# RelayBoard-Large-v11.net
KiCad netlist of a schematic drawn in EAGLE
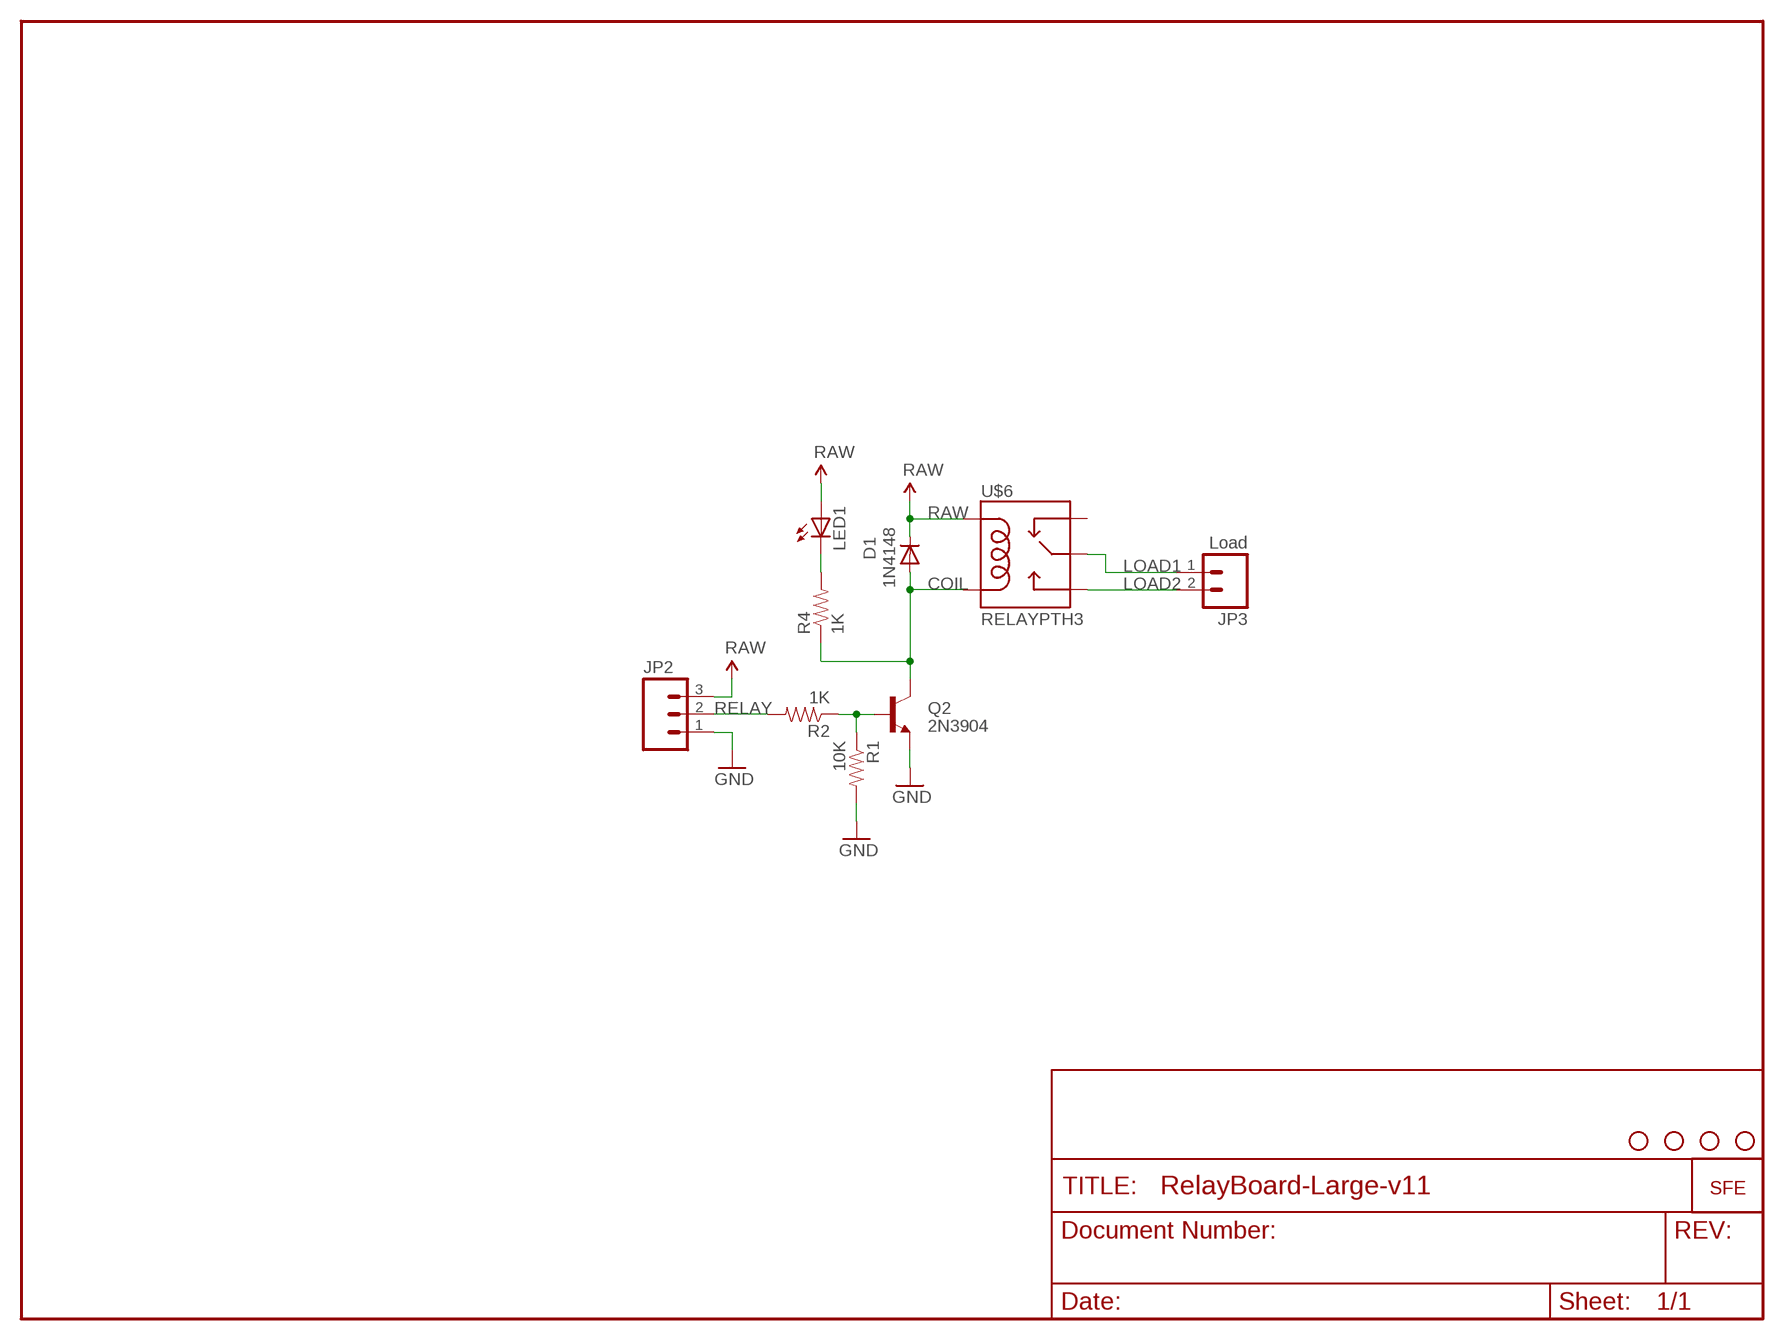
[diagram p0: schematic, sheet 1]

(export (version "E")
  (design (tool "Eeschema 10.0.6"))
  (components
    (comp (ref "D1")
      (value "1N4148")
      (footprint "eagle-import:DIODE-1N4148")
      (libsource (lib "eagle-import") (part "DIODE1N4148"))
    )
    (comp (ref "JP2")
      (value "M03SCREW")
      (footprint "eagle-import:SCREWTERMINAL-3.5MM-3")
      (libsource (lib "eagle-import") (part "M03SCREW"))
    )
    (comp (ref "JP3")
      (value "Load")
      (footprint "eagle-import:SCREWTERMINAL-5MM-2")
      (libsource (lib "eagle-import") (part "M025MM"))
    )
    (comp (ref "LED1")
      (value "LED5MM")
      (footprint "eagle-import:LED5MM")
      (libsource (lib "eagle-import") (part "LED5MM"))
    )
    (comp (ref "Q2")
      (value "2N3904")
      (footprint "eagle-import:TO-92")
      (libsource (lib "eagle-import") (part "TRANSISTOR_NPNTO92"))
    )
    (comp (ref "R1")
      (value "10K")
      (footprint "eagle-import:AXIAL-0.3")
      (libsource (lib "eagle-import") (part "RESISTORPTH1"))
    )
    (comp (ref "R2")
      (value "1K")
      (footprint "eagle-import:AXIAL-0.3")
      (libsource (lib "eagle-import") (part "RESISTORPTH1"))
    )
    (comp (ref "R4")
      (value "1K")
      (footprint "eagle-import:AXIAL-0.3")
      (libsource (lib "eagle-import") (part "RESISTORPTH1"))
    )
    (comp (ref "U$1")
      (value "LOGO-SFENEW")
      (footprint "eagle-import:SFE-NEW-WEBLOGO")
      (libsource (lib "eagle-import") (part "LOGO-SFENEW"))
    )
    (comp (ref "U$3")
      (value "STAND-OFF")
      (footprint "eagle-import:STAND-OFF")
      (libsource (lib "eagle-import") (part "STAND-OFF"))
    )
    (comp (ref "U$4")
      (value "STAND-OFF")
      (footprint "eagle-import:STAND-OFF")
      (libsource (lib "eagle-import") (part "STAND-OFF"))
    )
    (comp (ref "U$5")
      (value "STAND-OFF")
      (footprint "eagle-import:STAND-OFF")
      (libsource (lib "eagle-import") (part "STAND-OFF"))
    )
    (comp (ref "U$6")
      (value "RELAYPTH3")
      (footprint "eagle-import:RELAY-T9A-2")
      (libsource (lib "eagle-import") (part "RELAYPTH3"))
    )
    (comp (ref "U$7")
      (value "STAND-OFF")
      (footprint "eagle-import:STAND-OFF")
      (libsource (lib "eagle-import") (part "STAND-OFF"))
    )
  )
  (nets
    (net (code "1") (name "/COIL") (class "Default")
      (node (ref "D1") (pin "A") (pinfunction "A_A") (pintype "passive"))
      (node (ref "Q2") (pin "3") (pinfunction "C_3") (pintype "passive"))
      (node (ref "R4") (pin "P$1") (pinfunction "1_P$1") (pintype "passive"))
      (node (ref "U$6") (pin "COIL2") (pinfunction "COIL2_COIL2") (pintype "bidirectional"))
    )
    (net (code "2") (name "/LOAD1") (class "Default")
      (node (ref "JP3") (pin "1") (pinfunction "1_1") (pintype "passive"))
      (node (ref "U$6") (pin "MAIN") (pinfunction "MAIN_MAIN") (pintype "bidirectional"))
    )
    (net (code "3") (name "/LOAD2") (class "Default")
      (node (ref "JP3") (pin "2") (pinfunction "2_2") (pintype "passive"))
      (node (ref "U$6") (pin "NO") (pinfunction "NO_NO") (pintype "bidirectional"))
    )
    (net (code "4") (name "/RELAY") (class "Default")
      (node (ref "JP2") (pin "2") (pinfunction "2_2") (pintype "passive"))
      (node (ref "R2") (pin "P$2") (pinfunction "2_P$2") (pintype "passive"))
    )
    (net (code "5") (name "GND") (class "Default")
      (node (ref "JP2") (pin "1") (pinfunction "1_1") (pintype "passive"))
      (node (ref "Q2") (pin "1") (pinfunction "E_1") (pintype "passive"))
      (node (ref "R1") (pin "P$2") (pinfunction "2_P$2") (pintype "passive"))
    )
    (net (code "6") (name "Net-(LED1-C)") (class "Default")
      (node (ref "LED1") (pin "K") (pinfunction "C_K") (pintype "passive"))
      (node (ref "R4") (pin "P$2") (pinfunction "2_P$2") (pintype "passive"))
    )
    (net (code "7") (name "Net-(Q2-B)") (class "Default")
      (node (ref "Q2") (pin "2") (pinfunction "B_2") (pintype "passive"))
      (node (ref "R1") (pin "P$1") (pinfunction "1_P$1") (pintype "passive"))
      (node (ref "R2") (pin "P$1") (pinfunction "1_P$1") (pintype "passive"))
    )
    (net (code "8") (name "RAW") (class "Default")
      (node (ref "D1") (pin "C") (pinfunction "C_C") (pintype "passive"))
      (node (ref "JP2") (pin "3") (pinfunction "3_3") (pintype "passive"))
      (node (ref "LED1") (pin "A") (pinfunction "A_A") (pintype "passive"))
      (node (ref "U$6") (pin "COIL1") (pinfunction "COIL1_COIL1") (pintype "bidirectional"))
    )
    (net (code "9") (name "unconnected-(U$6-PadNC)") (class "Default")
      (node (ref "U$6") (pin "NC") (pinfunction "NC_NC") (pintype "bidirectional"))
    )
  )
)
